# LM399_breakout.net
KiCad netlist of a schematic drawn in EAGLE
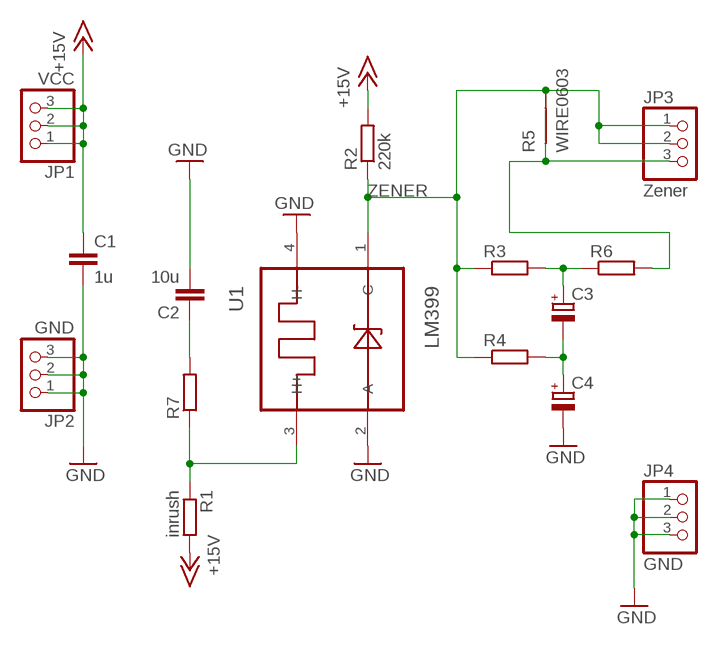
[diagram p0: schematic, sheet 1]

(export (version "E")
  (design (tool "Eeschema 10.0.6"))
  (components
    (comp (ref "C1")
      (value "1u")
      (footprint "eagle-import:C0805")
      (libsource (lib "eagle-import") (part "C-EUC0805"))
    )
    (comp (ref "C2")
      (value "10u")
      (footprint "eagle-import:C0805")
      (libsource (lib "eagle-import") (part "C-EUC0805"))
    )
    (comp (ref "C3")
      (value "CPOL-EUSMCC")
      (footprint "eagle-import:SMC_C")
      (libsource (lib "eagle-import") (part "CPOL-EUSMCC"))
    )
    (comp (ref "C4")
      (value "CPOL-EUSMCC")
      (footprint "eagle-import:SMC_C")
      (libsource (lib "eagle-import") (part "CPOL-EUSMCC"))
    )
    (comp (ref "JP1")
      (value "VCC")
      (footprint "eagle-import:1X03_SMALL")
      (libsource (lib "eagle-import") (part "PINHD-1X3TH_SMALL"))
    )
    (comp (ref "JP2")
      (value "GND")
      (footprint "eagle-import:1X03_SMALL")
      (libsource (lib "eagle-import") (part "PINHD-1X3TH_SMALL"))
    )
    (comp (ref "JP3")
      (value "Zener")
      (footprint "eagle-import:1X03_SMALL")
      (libsource (lib "eagle-import") (part "PINHD-1X3TH_SMALL"))
    )
    (comp (ref "JP4")
      (value "GND")
      (footprint "eagle-import:1X03_SMALL")
      (libsource (lib "eagle-import") (part "PINHD-1X3TH_SMALL"))
    )
    (comp (ref "R1")
      (value "inrush")
      (footprint "eagle-import:0207_10")
      (libsource (lib "eagle-import") (part "R-EU_0207/10"))
    )
    (comp (ref "R2")
      (value "220k")
      (footprint "eagle-import:0207_10")
      (libsource (lib "eagle-import") (part "R-EU_0207/10"))
    )
    (comp (ref "R3")
      (value "R-EU_0207/10")
      (footprint "eagle-import:0207_10")
      (libsource (lib "eagle-import") (part "R-EU_0207/10"))
    )
    (comp (ref "R4")
      (value "R-EU_0207/10")
      (footprint "eagle-import:0207_10")
      (libsource (lib "eagle-import") (part "R-EU_0207/10"))
    )
    (comp (ref "R5")
      (value "WIRE0603")
      (footprint "eagle-import:R0603_BRIDGE")
      (libsource (lib "eagle-import") (part "WIRE0603"))
    )
    (comp (ref "R6")
      (value "R-EU_0207/10")
      (footprint "eagle-import:0207_10")
      (libsource (lib "eagle-import") (part "R-EU_0207/10"))
    )
    (comp (ref "R7")
      (value "R-EU_R0603")
      (footprint "eagle-import:R0603")
      (libsource (lib "eagle-import") (part "R-EU_R0603"))
    )
    (comp (ref "U1")
      (value "LM399")
      (footprint "eagle-import:H4-TO46-4PIN")
      (libsource (lib "eagle-import") (part "LM399"))
    )
  )
  (nets
    (net (code "1") (name "+15V") (class "Default")
      (node (ref "C1") (pin "1") (pinfunction "1_1") (pintype "passive"))
      (node (ref "JP1") (pin "1") (pinfunction "1_1") (pintype "passive"))
      (node (ref "JP1") (pin "2") (pinfunction "2_2") (pintype "passive"))
      (node (ref "JP1") (pin "3") (pinfunction "3_3") (pintype "passive"))
      (node (ref "R1") (pin "2") (pinfunction "2_2") (pintype "passive"))
      (node (ref "R2") (pin "2") (pinfunction "2_2") (pintype "passive"))
    )
    (net (code "2") (name "/ZENER") (class "Default")
      (node (ref "JP3") (pin "1") (pinfunction "1_1") (pintype "passive"))
      (node (ref "JP3") (pin "2") (pinfunction "2_2") (pintype "passive"))
      (node (ref "JP3") (pin "3") (pinfunction "3_3") (pintype "passive"))
      (node (ref "R2") (pin "1") (pinfunction "1_1") (pintype "passive"))
      (node (ref "R3") (pin "1") (pinfunction "1_1") (pintype "passive"))
      (node (ref "R4") (pin "1") (pinfunction "1_1") (pintype "passive"))
      (node (ref "R5") (pin "1") (pinfunction "1_1") (pintype "passive"))
      (node (ref "R5") (pin "2") (pinfunction "2_2") (pintype "passive"))
      (node (ref "R6") (pin "2") (pinfunction "2_2") (pintype "passive"))
      (node (ref "U1") (pin "1") (pinfunction "C_1") (pintype "input"))
    )
    (net (code "3") (name "GND") (class "Default")
      (node (ref "C1") (pin "2") (pinfunction "2_2") (pintype "passive"))
      (node (ref "C2") (pin "2") (pinfunction "2_2") (pintype "passive"))
      (node (ref "C4") (pin "-") (pinfunction "-_-") (pintype "passive"))
      (node (ref "JP2") (pin "1") (pinfunction "1_1") (pintype "passive"))
      (node (ref "JP2") (pin "2") (pinfunction "2_2") (pintype "passive"))
      (node (ref "JP2") (pin "3") (pinfunction "3_3") (pintype "passive"))
      (node (ref "JP4") (pin "1") (pinfunction "1_1") (pintype "passive"))
      (node (ref "JP4") (pin "2") (pinfunction "2_2") (pintype "passive"))
      (node (ref "JP4") (pin "3") (pinfunction "3_3") (pintype "passive"))
      (node (ref "U1") (pin "2") (pinfunction "A_2") (pintype "input"))
      (node (ref "U1") (pin "4") (pinfunction "H-_4") (pintype "input"))
    )
    (net (code "4") (name "Net-(C2-Pad1)") (class "Default")
      (node (ref "C2") (pin "1") (pinfunction "1_1") (pintype "passive"))
      (node (ref "R7") (pin "2") (pinfunction "2_2") (pintype "passive"))
    )
    (net (code "5") (name "Net-(C3-Pad+)") (class "Default")
      (node (ref "C3") (pin "+") (pinfunction "+_+") (pintype "passive"))
      (node (ref "R3") (pin "2") (pinfunction "2_2") (pintype "passive"))
      (node (ref "R6") (pin "1") (pinfunction "1_1") (pintype "passive"))
    )
    (net (code "6") (name "Net-(C3-Pad-)") (class "Default")
      (node (ref "C3") (pin "-") (pinfunction "-_-") (pintype "passive"))
      (node (ref "C4") (pin "+") (pinfunction "+_+") (pintype "passive"))
      (node (ref "R4") (pin "2") (pinfunction "2_2") (pintype "passive"))
    )
    (net (code "7") (name "Net-(U1-H+)") (class "Default")
      (node (ref "R1") (pin "1") (pinfunction "1_1") (pintype "passive"))
      (node (ref "R7") (pin "1") (pinfunction "1_1") (pintype "passive"))
      (node (ref "U1") (pin "3") (pinfunction "H+_3") (pintype "input"))
    )
  )
)
